# AEMLIC_V3.net
KiCad netlist of a schematic drawn in EAGLE
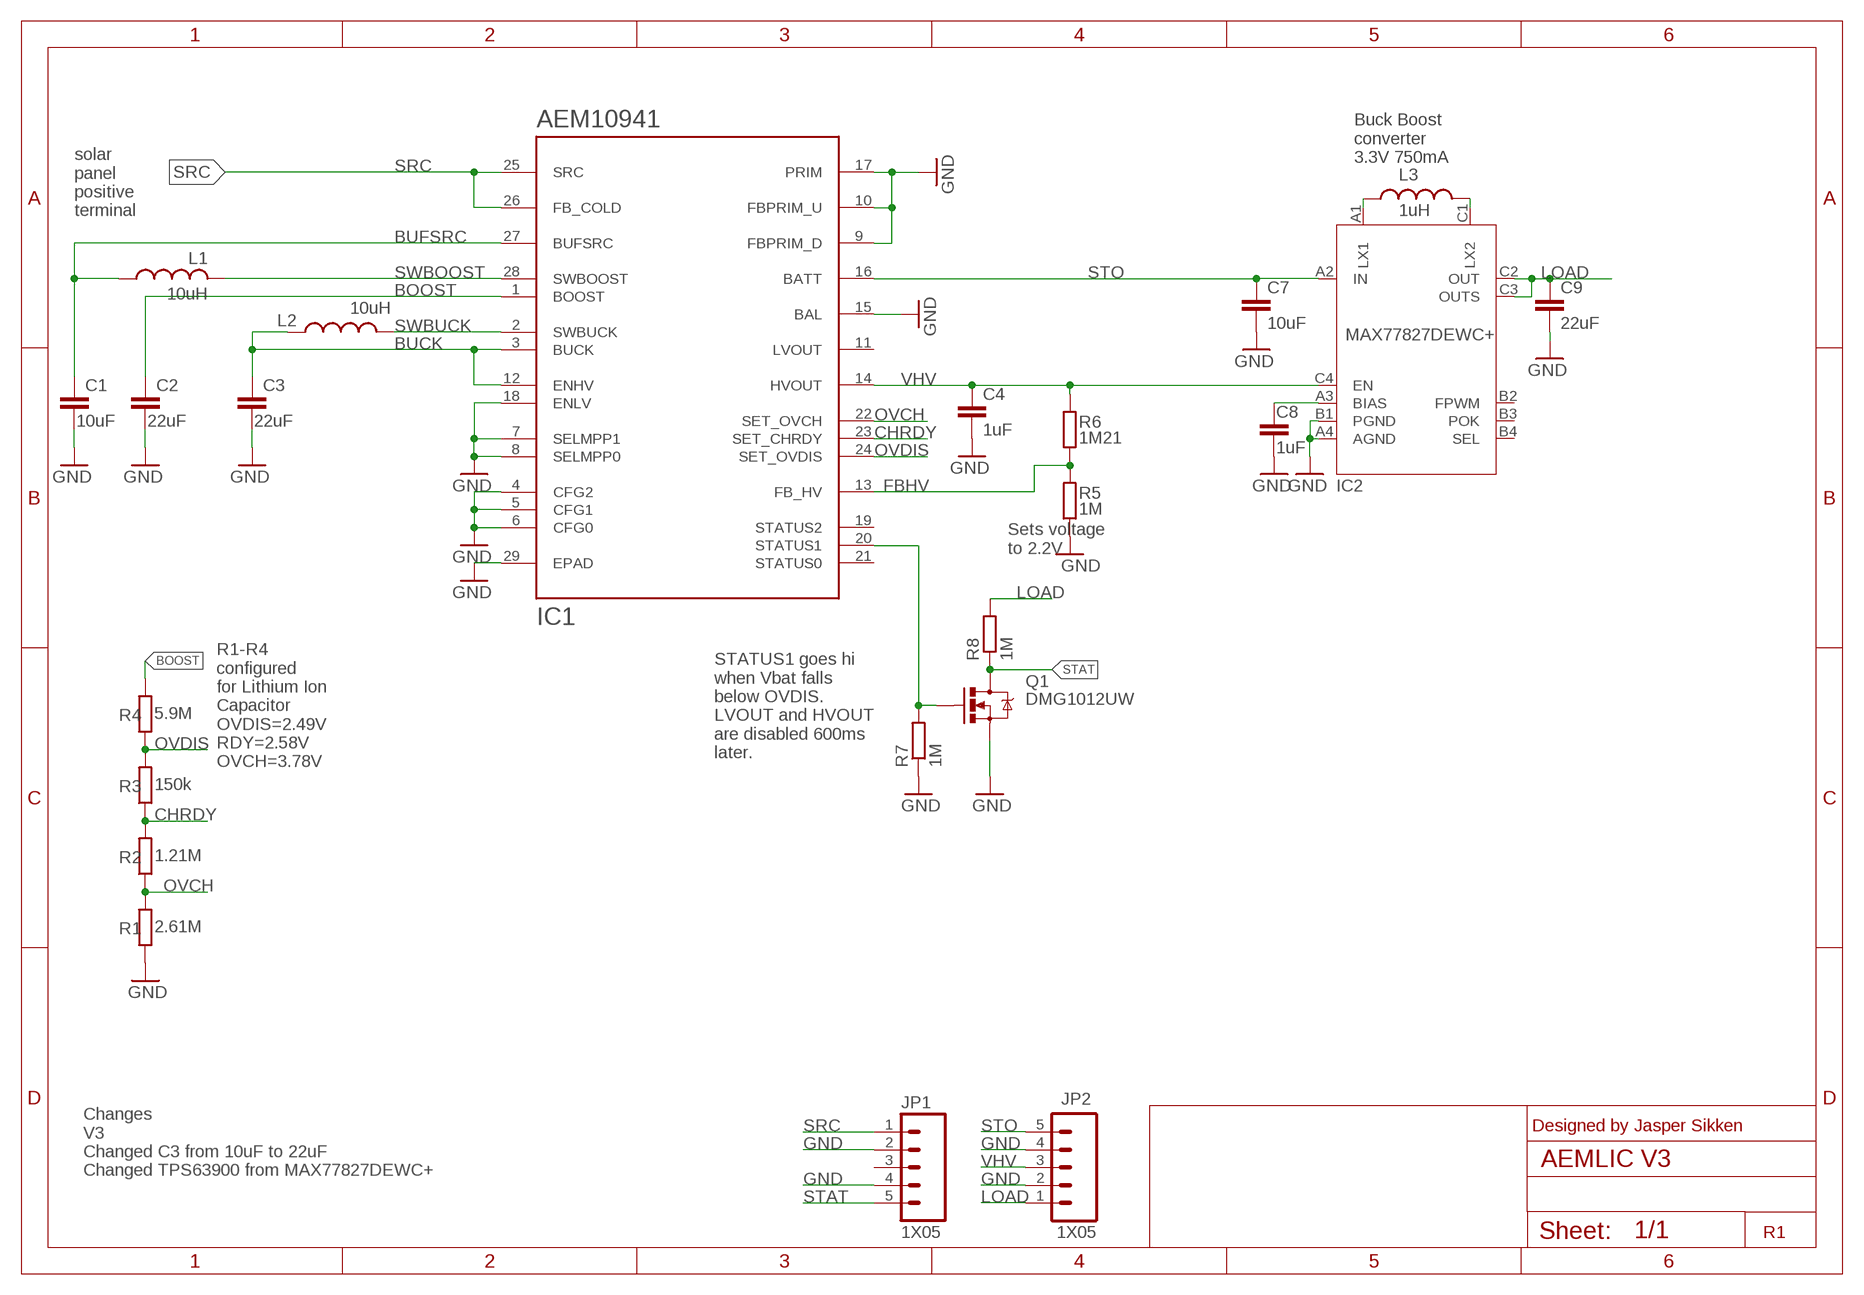
[diagram p0: schematic, sheet 1]

(export (version "E")
  (design (tool "Eeschema 10.0.6"))
  (components
    (comp (ref "C1")
      (value "10uF")
      (footprint "eagle-import:C0603")
      (fields
        (field (name "MF") "Taiyo Yuden")
        (field (name "MPN") "LMK107BBJ106MALT")
        (field (name "MF_1") "KEYSTONE")
        (field (name "MPN_1") "1049P")
      )
      (libsource (lib "eagle-import") (part "TSEM_C0603_10UF"))
    )
    (comp (ref "C2")
      (value "22uF")
      (footprint "eagle-import:C0603")
      (fields
        (field (name "MF") "Murata")
        (field (name "MPN") "GRM188R61A226ME15D")
        (field (name "MF_1") "TDK")
        (field (name "MPN_1") "CGA5L1X7S1A226M160AC")
      )
      (libsource (lib "eagle-import") (part "TSEM_C0603_22UF"))
    )
    (comp (ref "C3")
      (value "22uF")
      (footprint "eagle-import:C0603")
      (fields
        (field (name "MF") "Taiyo Yuden")
        (field (name "MPN") "LMK107BBJ106MALT")
        (field (name "MF_1") "KEYSTONE")
        (field (name "MPN_1") "1049P")
      )
      (libsource (lib "eagle-import") (part "TSEM_C0603_10UF"))
    )
    (comp (ref "C4")
      (value "1uF")
      (footprint "eagle-import:C0603")
      (fields (field (name "MF") "Taiyo Yuden") (field (name "MPN") "LMK107BBJ106MALT"))
      (libsource (lib "eagle-import") (part "TSEM_C0603_10UF"))
    )
    (comp (ref "C7")
      (value "10uF")
      (footprint "eagle-import:C0603")
      (fields (field (name "MF") "Taiyo Yuden") (field (name "MPN") "LMK107BBJ106MALT"))
      (libsource (lib "eagle-import") (part "TSEM_C0603_10UF"))
    )
    (comp (ref "C8")
      (value "1uF")
      (footprint "eagle-import:C0603")
      (libsource (lib "eagle-import") (part "C0603_1UF"))
    )
    (comp (ref "C9")
      (value "22uF")
      (footprint "eagle-import:C0603")
      (fields (field (name "MF") "Murata") (field (name "MPN") "GRM188R61A226ME15D"))
      (libsource (lib "eagle-import") (part "TSEM_C0603_22UF"))
    )
    (comp (ref "IC1")
      (value "AEM10941")
      (footprint "eagle-import:QFN50P505X505X90-28")
      (fields (field (name "MF") "e-peas"))
      (libsource (lib "eagle-import") (part "AEM10941"))
    )
    (comp (ref "IC2")
      (value "MAX77827DEWC+")
      (footprint "eagle-import:WLP-12P-0.4PITCH")
      (fields (field (name "MANUFACTURER") "Maxim Integrated") (field (name "MPN") "MAX77827DEWC+T"))
      (libsource (lib "eagle-import") (part "MAX77827DEWC+"))
    )
    (comp (ref "JP1")
      (value "1X05")
      (footprint "eagle-import:1X05_2.54MM_ROUND_NOSILK")
      (libsource (lib "eagle-import") (part "1X05"))
    )
    (comp (ref "JP2")
      (value "1X05")
      (footprint "eagle-import:1X05_2.54MM_ROUND_NOSILK")
      (libsource (lib "eagle-import") (part "1X05"))
    )
    (comp (ref "L1")
      (value "10uH")
      (footprint "eagle-import:L_74404032100")
      (fields (field (name "MF") "Wurth") (field (name "MPN") "74404032100"))
      (libsource (lib "eagle-import") (part "L3X3"))
    )
    (comp (ref "L2")
      (value "10uH")
      (footprint "eagle-import:L0603")
      (fields
        (field (name "MF") "TDK")
        (field (name "MPN") "MLZ1608M100WT")
        (field (name "MF_1") "TAIYO YUDEN")
        (field (name "MPN_1") "CK2125100M-T")
      )
      (libsource (lib "eagle-import") (part "TSEM_L0603_10UH"))
    )
    (comp (ref "L3")
      (value "1uH")
      (footprint "eagle-import:L_1008_[2520]")
      (fields (field (name "MF") "murata") (field (name "MPN") "DFE252012F-1R0M#"))
      (libsource (lib "eagle-import") (part "L3"))
    )
    (comp (ref "Q1")
      (value "DMG1012UW")
      (footprint "eagle-import:SOT323")
      (fields (field (name "MF") "Diodes") (field (name "MPN") "DMG1012UW-7"))
      (libsource (lib "eagle-import") (part "MOSFET-N-CHANNEL_DMG1012UW"))
    )
    (comp (ref "R1")
      (value "2.61M")
      (footprint "eagle-import:R0402")
      (fields (field (name "MF") "Walsin") (field (name "MPN") "WR04X1004FTL"))
      (libsource (lib "eagle-import") (part "R0402_1M"))
    )
    (comp (ref "R2")
      (value "1.21M")
      (footprint "eagle-import:R0402")
      (fields (field (name "MF") "Walsin") (field (name "MPN") "WR04X1004FTL"))
      (libsource (lib "eagle-import") (part "R0402_1M"))
    )
    (comp (ref "R3")
      (value "150k")
      (footprint "eagle-import:R0402")
      (fields (field (name "MF") "Walsin") (field (name "MPN") "WR04X1004FTL"))
      (libsource (lib "eagle-import") (part "R0402_1M"))
    )
    (comp (ref "R4")
      (value "5.9M")
      (footprint "eagle-import:R0402")
      (fields (field (name "MF") "Walsin") (field (name "MPN") "WR04X1004FTL"))
      (libsource (lib "eagle-import") (part "R0402_1M"))
    )
    (comp (ref "R5")
      (value "1M")
      (footprint "eagle-import:R0402")
      (fields (field (name "MF") "Walsin") (field (name "MPN") "WR04X1004FTL"))
      (libsource (lib "eagle-import") (part "R0402_1M"))
    )
    (comp (ref "R6")
      (value "1M21")
      (footprint "eagle-import:R0402")
      (fields (field (name "MF") "Walsin") (field (name "MPN") "WR04X1004FTL"))
      (libsource (lib "eagle-import") (part "R0402_1M"))
    )
    (comp (ref "R7")
      (value "1M")
      (footprint "eagle-import:R0402")
      (fields (field (name "MF") "Walsin") (field (name "MPN") "WR04X1004FTL"))
      (libsource (lib "eagle-import") (part "R0402_1M"))
    )
    (comp (ref "R8")
      (value "1M")
      (footprint "eagle-import:R0402")
      (fields (field (name "MF") "Walsin") (field (name "MPN") "WR04X1004FTL"))
      (libsource (lib "eagle-import") (part "R0402_1M"))
    )
  )
  (nets
    (net (code "1") (name "/BUCK") (class "Default")
      (node (ref "C3") (pin "1") (pinfunction "1_1") (pintype "passive"))
      (node (ref "IC1") (pin "12") (pinfunction "ENHV_12") (pintype "bidirectional"))
      (node (ref "IC1") (pin "3") (pinfunction "BUCK_3") (pintype "bidirectional"))
      (node (ref "L2") (pin "1") (pinfunction "1_1") (pintype "passive"))
    )
    (net (code "2") (name "/BUFSRC") (class "Default")
      (node (ref "C1") (pin "1") (pinfunction "1_1") (pintype "passive"))
      (node (ref "IC1") (pin "27") (pinfunction "BUFSRC_27") (pintype "power_in"))
      (node (ref "L1") (pin "1") (pinfunction "1_1") (pintype "passive"))
    )
    (net (code "3") (name "/CHRDY") (class "Default")
      (node (ref "IC1") (pin "23") (pinfunction "SET_CHRDY_23") (pintype "bidirectional"))
      (node (ref "R2") (pin "2") (pinfunction "2_2") (pintype "passive"))
      (node (ref "R3") (pin "1") (pinfunction "1_1") (pintype "passive"))
    )
    (net (code "4") (name "/FBHV") (class "Default")
      (node (ref "IC1") (pin "13") (pinfunction "FB_HV_13") (pintype "bidirectional"))
      (node (ref "R5") (pin "2") (pinfunction "2_2") (pintype "passive"))
      (node (ref "R6") (pin "1") (pinfunction "1_1") (pintype "passive"))
    )
    (net (code "5") (name "/LOAD") (class "Default")
      (node (ref "C9") (pin "1") (pinfunction "1_1") (pintype "passive"))
      (node (ref "IC2") (pin "C2") (pinfunction "OUT_C2") (pintype "bidirectional"))
      (node (ref "IC2") (pin "C3") (pinfunction "OUTS_C3") (pintype "bidirectional"))
      (node (ref "JP2") (pin "1") (pinfunction "1_1") (pintype "passive"))
      (node (ref "R8") (pin "2") (pinfunction "2_2") (pintype "passive"))
    )
    (net (code "6") (name "/OVCH") (class "Default")
      (node (ref "IC1") (pin "22") (pinfunction "SET_OVCH_22") (pintype "bidirectional"))
      (node (ref "R1") (pin "2") (pinfunction "2_2") (pintype "passive"))
      (node (ref "R2") (pin "1") (pinfunction "1_1") (pintype "passive"))
    )
    (net (code "7") (name "/OVDIS") (class "Default")
      (node (ref "IC1") (pin "24") (pinfunction "SET_OVDIS_24") (pintype "bidirectional"))
      (node (ref "R3") (pin "2") (pinfunction "2_2") (pintype "passive"))
      (node (ref "R4") (pin "1") (pinfunction "1_1") (pintype "passive"))
    )
    (net (code "8") (name "/STO") (class "Default")
      (node (ref "C7") (pin "1") (pinfunction "1_1") (pintype "passive"))
      (node (ref "IC1") (pin "16") (pinfunction "BATT_16") (pintype "bidirectional"))
      (node (ref "IC2") (pin "A2") (pinfunction "IN_A2") (pintype "bidirectional"))
      (node (ref "JP2") (pin "5") (pinfunction "5_5") (pintype "passive"))
    )
    (net (code "9") (name "/SWBOOST") (class "Default")
      (node (ref "IC1") (pin "28") (pinfunction "SWBOOST_28") (pintype "power_in"))
      (node (ref "L1") (pin "2") (pinfunction "2_2") (pintype "passive"))
    )
    (net (code "10") (name "/SWBUCK") (class "Default")
      (node (ref "IC1") (pin "2") (pinfunction "SWBUCK_2") (pintype "bidirectional"))
      (node (ref "L2") (pin "2") (pinfunction "2_2") (pintype "passive"))
    )
    (net (code "11") (name "/VHV") (class "Default")
      (node (ref "C4") (pin "1") (pinfunction "1_1") (pintype "passive"))
      (node (ref "IC1") (pin "14") (pinfunction "HVOUT_14") (pintype "bidirectional"))
      (node (ref "IC2") (pin "C4") (pinfunction "EN_C4") (pintype "bidirectional"))
      (node (ref "JP2") (pin "3") (pinfunction "3_3") (pintype "passive"))
      (node (ref "R6") (pin "2") (pinfunction "2_2") (pintype "passive"))
    )
    (net (code "12") (name "BOOST") (class "Default")
      (node (ref "C2") (pin "1") (pinfunction "1_1") (pintype "passive"))
      (node (ref "IC1") (pin "1") (pinfunction "BOOST_1") (pintype "bidirectional"))
      (node (ref "R4") (pin "2") (pinfunction "2_2") (pintype "passive"))
    )
    (net (code "13") (name "GND") (class "Default")
      (node (ref "C1") (pin "2") (pinfunction "2_2") (pintype "passive"))
      (node (ref "C2") (pin "2") (pinfunction "2_2") (pintype "passive"))
      (node (ref "C3") (pin "2") (pinfunction "2_2") (pintype "passive"))
      (node (ref "C4") (pin "2") (pinfunction "2_2") (pintype "passive"))
      (node (ref "C7") (pin "2") (pinfunction "2_2") (pintype "passive"))
      (node (ref "C8") (pin "2") (pinfunction "2_2") (pintype "passive"))
      (node (ref "C9") (pin "2") (pinfunction "2_2") (pintype "passive"))
      (node (ref "IC1") (pin "10") (pinfunction "FBPRIM_U_10") (pintype "bidirectional"))
      (node (ref "IC1") (pin "15") (pinfunction "BAL_15") (pintype "bidirectional"))
      (node (ref "IC1") (pin "17") (pinfunction "PRIM_17") (pintype "bidirectional"))
      (node (ref "IC1") (pin "18") (pinfunction "ENLV_18") (pintype "bidirectional"))
      (node (ref "IC1") (pin "29") (pinfunction "EPAD_29") (pintype "power_in"))
      (node (ref "IC1") (pin "4") (pinfunction "CFG2_4") (pintype "bidirectional"))
      (node (ref "IC1") (pin "5") (pinfunction "CFG1_5") (pintype "bidirectional"))
      (node (ref "IC1") (pin "6") (pinfunction "CFG0_6") (pintype "bidirectional"))
      (node (ref "IC1") (pin "7") (pinfunction "SELMPP1_7") (pintype "bidirectional"))
      (node (ref "IC1") (pin "8") (pinfunction "SELMPP0_8") (pintype "bidirectional"))
      (node (ref "IC1") (pin "9") (pinfunction "FBPRIM_D_9") (pintype "bidirectional"))
      (node (ref "IC2") (pin "A4") (pinfunction "AGND_A4") (pintype "bidirectional"))
      (node (ref "IC2") (pin "B1") (pinfunction "PGND_B1") (pintype "bidirectional"))
      (node (ref "JP1") (pin "2") (pinfunction "2_2") (pintype "passive"))
      (node (ref "JP1") (pin "4") (pinfunction "4_4") (pintype "passive"))
      (node (ref "JP2") (pin "2") (pinfunction "2_2") (pintype "passive"))
      (node (ref "JP2") (pin "4") (pinfunction "4_4") (pintype "passive"))
      (node (ref "Q1") (pin "2") (pinfunction "S_2") (pintype "passive"))
      (node (ref "R1") (pin "1") (pinfunction "1_1") (pintype "passive"))
      (node (ref "R5") (pin "1") (pinfunction "1_1") (pintype "passive"))
      (node (ref "R7") (pin "1") (pinfunction "1_1") (pintype "passive"))
    )
    (net (code "14") (name "Net-(IC1-STATUS1)") (class "Default")
      (node (ref "IC1") (pin "20") (pinfunction "STATUS1_20") (pintype "bidirectional"))
      (node (ref "Q1") (pin "1") (pinfunction "G_1") (pintype "passive"))
      (node (ref "R7") (pin "2") (pinfunction "2_2") (pintype "passive"))
    )
    (net (code "15") (name "Net-(IC2-BIAS)") (class "Default")
      (node (ref "C8") (pin "1") (pinfunction "1_1") (pintype "passive"))
      (node (ref "IC2") (pin "A3") (pinfunction "BIAS_A3") (pintype "bidirectional"))
    )
    (net (code "16") (name "Net-(IC2-LX1)") (class "Default")
      (node (ref "IC2") (pin "A1") (pinfunction "LX1_A1") (pintype "bidirectional"))
      (node (ref "L3") (pin "2") (pinfunction "1_2") (pintype "passive"))
    )
    (net (code "17") (name "Net-(IC2-LX2)") (class "Default")
      (node (ref "IC2") (pin "C1") (pinfunction "LX2_C1") (pintype "bidirectional"))
      (node (ref "L3") (pin "1") (pinfunction "2_1") (pintype "passive"))
    )
    (net (code "18") (name "SRC") (class "Default")
      (node (ref "IC1") (pin "25") (pinfunction "SRC_25") (pintype "power_in"))
      (node (ref "IC1") (pin "26") (pinfunction "FB_COLD_26") (pintype "input"))
      (node (ref "JP1") (pin "1") (pinfunction "1_1") (pintype "passive"))
    )
    (net (code "19") (name "STAT") (class "Default")
      (node (ref "JP1") (pin "5") (pinfunction "5_5") (pintype "passive"))
      (node (ref "Q1") (pin "3") (pinfunction "D_3") (pintype "passive"))
      (node (ref "R8") (pin "1") (pinfunction "1_1") (pintype "passive"))
    )
    (net (code "20") (name "unconnected-(IC1-LVOUT-Pad11)") (class "Default")
      (node (ref "IC1") (pin "11") (pinfunction "LVOUT_11") (pintype "bidirectional"))
    )
    (net (code "21") (name "unconnected-(IC1-STATUS0-Pad21)") (class "Default")
      (node (ref "IC1") (pin "21") (pinfunction "STATUS0_21") (pintype "bidirectional"))
    )
    (net (code "22") (name "unconnected-(IC1-STATUS2-Pad19)") (class "Default")
      (node (ref "IC1") (pin "19") (pinfunction "STATUS2_19") (pintype "bidirectional"))
    )
    (net (code "23") (name "unconnected-(IC2-FPWM-PadB2)") (class "Default")
      (node (ref "IC2") (pin "B2") (pinfunction "FPWM_B2") (pintype "bidirectional"))
    )
    (net (code "24") (name "unconnected-(IC2-POK-PadB3)") (class "Default")
      (node (ref "IC2") (pin "B3") (pinfunction "POK_B3") (pintype "bidirectional"))
    )
    (net (code "25") (name "unconnected-(IC2-SEL-PadB4)") (class "Default")
      (node (ref "IC2") (pin "B4") (pinfunction "SEL_B4") (pintype "bidirectional"))
    )
    (net (code "26") (name "unconnected-(JP1-Pad3)") (class "Default")
      (node (ref "JP1") (pin "3") (pinfunction "3_3") (pintype "passive"))
    )
  )
)
